# Adafruit_2_13in_Tri-Color_eInk_FeatherWi.net
KiCad netlist of a schematic drawn in EAGLE
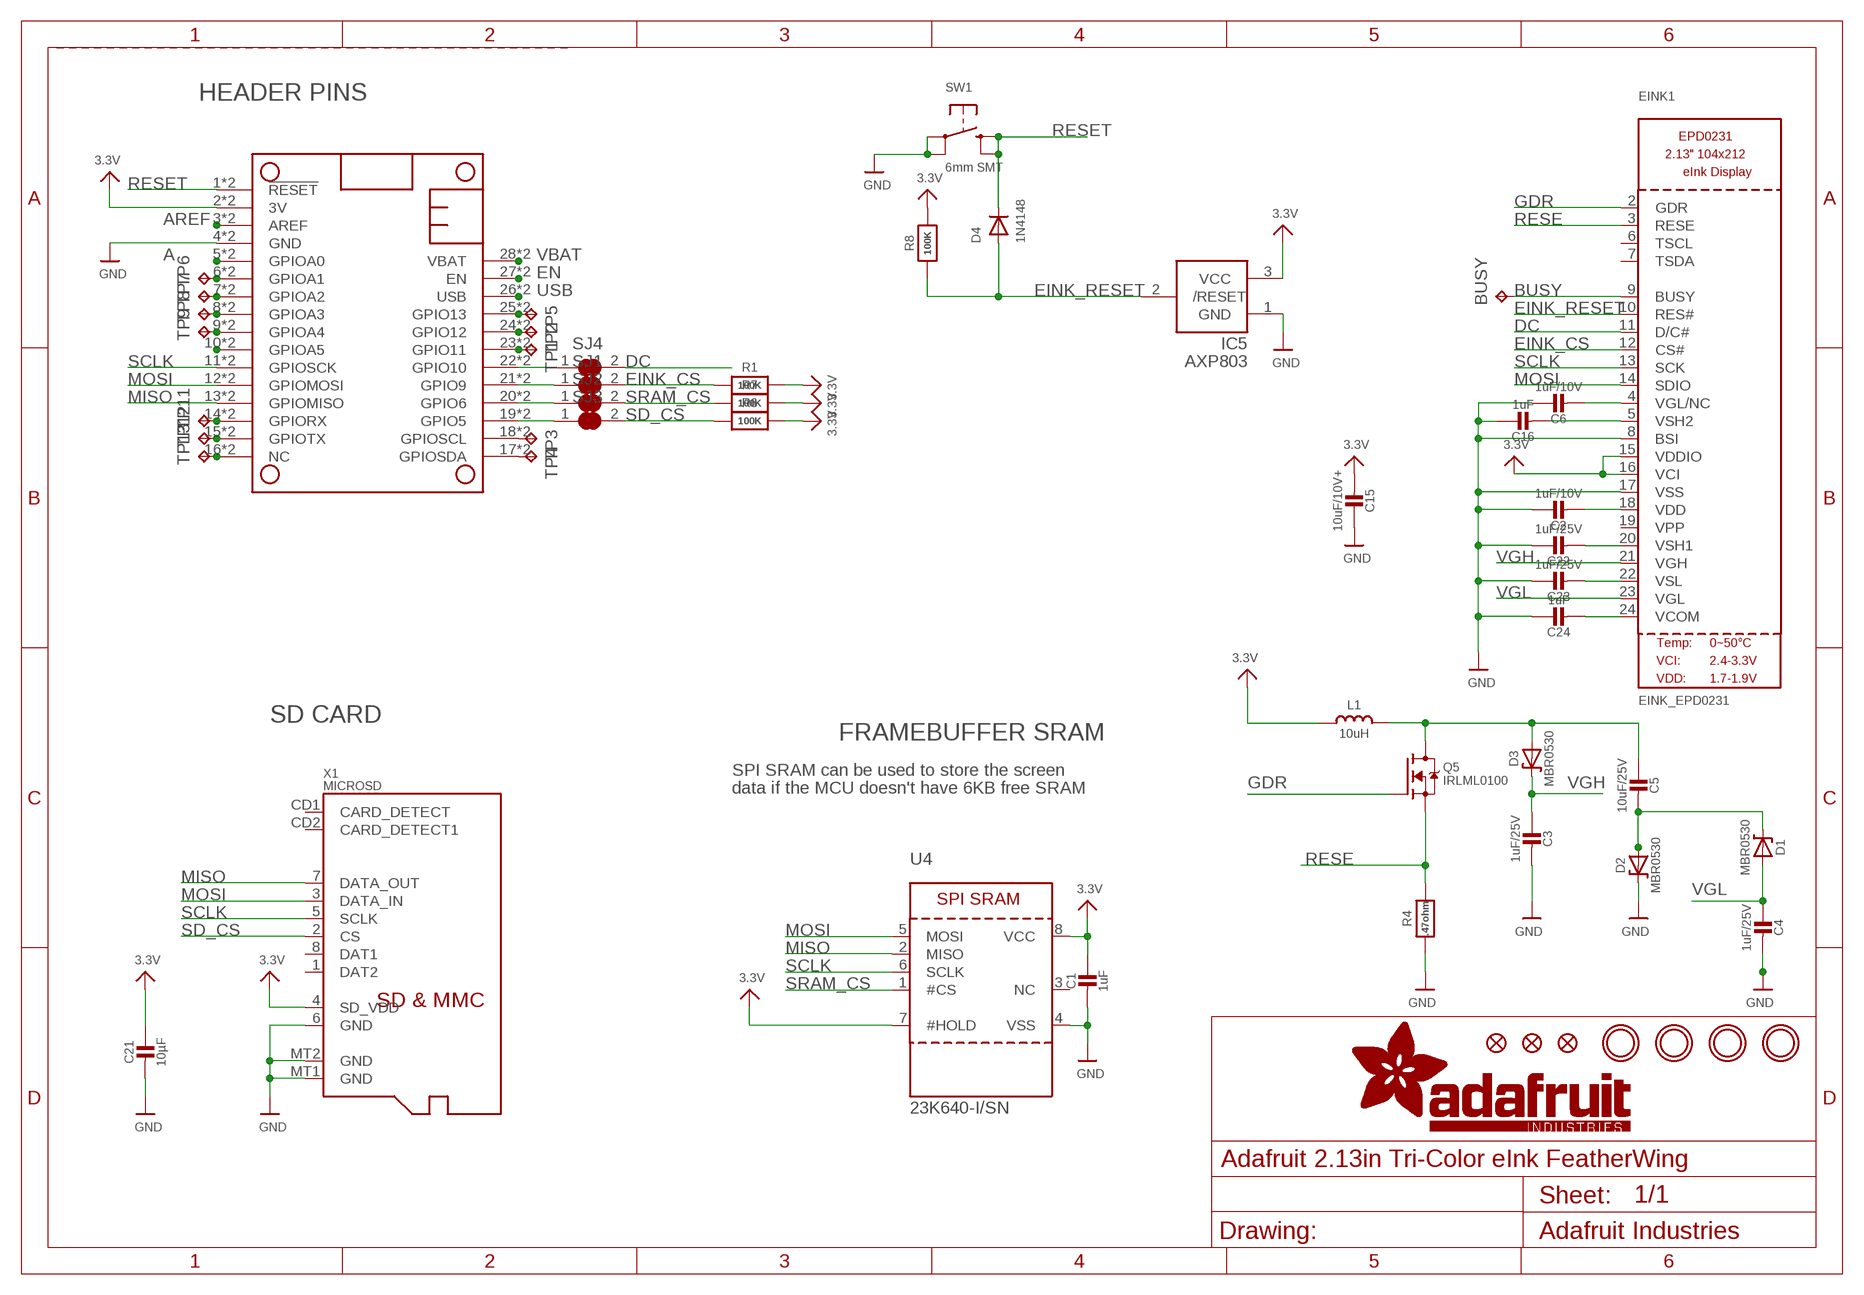
[diagram p0: schematic, sheet 1]

(export (version "E")
  (design (tool "Eeschema 10.0.6"))
  (components
    (comp (ref "BUSY")
      (value "TPTP15SQ")
      (footprint "eagle-import:TP15SQ")
      (libsource (lib "eagle-import") (part "TPTP15SQ"))
    )
    (comp (ref "C1")
      (value "1uF")
      (footprint "eagle-import:0805_10MGAP")
      (libsource (lib "eagle-import") (part "CAP_CERAMIC0805_10MGAP"))
    )
    (comp (ref "C2")
      (value "1uF/10V")
      (footprint "eagle-import:0805-NO")
      (libsource (lib "eagle-import") (part "CAP_CERAMIC0805-NOOUTLINE"))
    )
    (comp (ref "C3")
      (value "1uF/25V")
      (footprint "eagle-import:0805-NO")
      (libsource (lib "eagle-import") (part "CAP_CERAMIC0805-NOOUTLINE"))
    )
    (comp (ref "C4")
      (value "1uF/25V")
      (footprint "eagle-import:0805-NO")
      (libsource (lib "eagle-import") (part "CAP_CERAMIC0805-NOOUTLINE"))
    )
    (comp (ref "C5")
      (value "10uF/25V")
      (footprint "eagle-import:0805-NO")
      (libsource (lib "eagle-import") (part "CAP_CERAMIC0805-NOOUTLINE"))
    )
    (comp (ref "C6")
      (value "1uF/10V")
      (footprint "eagle-import:0805-NO")
      (libsource (lib "eagle-import") (part "CAP_CERAMIC0805-NOOUTLINE"))
    )
    (comp (ref "C15")
      (value "10uF/10V+")
      (footprint "eagle-import:0805-NO")
      (libsource (lib "eagle-import") (part "CAP_CERAMIC0805-NOOUTLINE"))
    )
    (comp (ref "C16")
      (value "1uF")
      (footprint "eagle-import:0805-NO")
      (libsource (lib "eagle-import") (part "CAP_CERAMIC0805-NOOUTLINE"))
    )
    (comp (ref "C21")
      (value "10µF")
      (footprint "eagle-import:0805-NO")
      (libsource (lib "eagle-import") (part "CAP_CERAMIC0805-NOOUTLINE"))
    )
    (comp (ref "C22")
      (value "1uF/25V")
      (footprint "eagle-import:0805-NO")
      (libsource (lib "eagle-import") (part "CAP_CERAMIC0805-NOOUTLINE"))
    )
    (comp (ref "C23")
      (value "1uF/25V")
      (footprint "eagle-import:0805-NO")
      (libsource (lib "eagle-import") (part "CAP_CERAMIC0805-NOOUTLINE"))
    )
    (comp (ref "C24")
      (value "1uF")
      (footprint "eagle-import:0805-NO")
      (libsource (lib "eagle-import") (part "CAP_CERAMIC0805-NOOUTLINE"))
    )
    (comp (ref "D1")
      (value "MBR0530")
      (footprint "eagle-import:SOD-123")
      (libsource (lib "eagle-import") (part "DIODE-SCHOTTKYSOD-123"))
    )
    (comp (ref "D2")
      (value "MBR0530")
      (footprint "eagle-import:SOD-123")
      (libsource (lib "eagle-import") (part "DIODE-SCHOTTKYSOD-123"))
    )
    (comp (ref "D3")
      (value "MBR0530")
      (footprint "eagle-import:SOD-123")
      (libsource (lib "eagle-import") (part "DIODE-SCHOTTKYSOD-123"))
    )
    (comp (ref "D4")
      (value "1N4148")
      (footprint "eagle-import:SOD-323F")
      (libsource (lib "eagle-import") (part "DIODESOD-323F"))
    )
    (comp (ref "EINK1")
      (value "EINK_EPD0231")
      (footprint "eagle-import:EINK_213IN_104X212")
      (libsource (lib "eagle-import") (part "EINK_EPD0231"))
    )
    (comp (ref "FID1")
      (value "FIDUCIAL_1MM")
      (footprint "eagle-import:FIDUCIAL_1MM")
      (libsource (lib "eagle-import") (part "FIDUCIAL_1MM"))
    )
    (comp (ref "FID2")
      (value "FIDUCIAL_1MM")
      (footprint "eagle-import:FIDUCIAL_1MM")
      (libsource (lib "eagle-import") (part "FIDUCIAL_1MM"))
    )
    (comp (ref "FID3")
      (value "FIDUCIAL_1MM")
      (footprint "eagle-import:FIDUCIAL_1MM")
      (libsource (lib "eagle-import") (part "FIDUCIAL_1MM"))
    )
    (comp (ref "IC5")
      (value "AXP803")
      (footprint "eagle-import:SOT23")
      (libsource (lib "eagle-import") (part "AXP083-SAG"))
    )
    (comp (ref "L1")
      (value "10uH")
      (footprint "eagle-import:INDUCTOR_4X4MM_NR401")
      (libsource (lib "eagle-import") (part "INDUCTORNR401"))
    )
    (comp (ref "MS1")
      (value "FEATHERWING_SMTDUALNOHOLES")
      (footprint "eagle-import:FEATHERWING_SMT_NOHOLES")
      (libsource (lib "eagle-import") (part "FEATHERWING_SMTDUALNOHOLES"))
    )
    (comp (ref "Q5")
      (value "IRLML0100")
      (footprint "eagle-import:SOT23-3")
      (libsource (lib "eagle-import") (part "IRLML2060TRPBF"))
    )
    (comp (ref "R1")
      (value "100K")
      (footprint "eagle-import:0603-NO")
      (libsource (lib "eagle-import") (part "RESISTOR_0603_NOOUT"))
    )
    (comp (ref "R4")
      (value ".47ohm")
      (footprint "eagle-import:0805_10MGAP")
      (libsource (lib "eagle-import") (part "RESISTOR0805_10MGAP"))
    )
    (comp (ref "R6")
      (value "100K")
      (footprint "eagle-import:0603-NO")
      (libsource (lib "eagle-import") (part "RESISTOR_0603_NOOUT"))
    )
    (comp (ref "R7")
      (value "100K")
      (footprint "eagle-import:0603-NO")
      (libsource (lib "eagle-import") (part "RESISTOR_0603_NOOUT"))
    )
    (comp (ref "R8")
      (value "100K")
      (footprint "eagle-import:0603-NO")
      (libsource (lib "eagle-import") (part "RESISTOR_0603_NOOUT"))
    )
    (comp (ref "SJ1")
      (value "SOLDERJUMPER_CLOSED")
      (footprint "eagle-import:SOLDERJUMPER_CLOSEDWIRE")
      (libsource (lib "eagle-import") (part "SOLDERJUMPER_CLOSED"))
    )
    (comp (ref "SJ2")
      (value "SOLDERJUMPER_CLOSED")
      (footprint "eagle-import:SOLDERJUMPER_CLOSEDWIRE")
      (libsource (lib "eagle-import") (part "SOLDERJUMPER_CLOSED"))
    )
    (comp (ref "SJ3")
      (value "SOLDERJUMPER_CLOSED")
      (footprint "eagle-import:SOLDERJUMPER_CLOSEDWIRE")
      (libsource (lib "eagle-import") (part "SOLDERJUMPER_CLOSED"))
    )
    (comp (ref "SJ4")
      (value "SOLDERJUMPER_CLOSED")
      (footprint "eagle-import:SOLDERJUMPER_CLOSEDWIRE")
      (libsource (lib "eagle-import") (part "SOLDERJUMPER_CLOSED"))
    )
    (comp (ref "SW1")
      (value "6mm SMT")
      (footprint "eagle-import:EVQ-Q2_SMALLER")
      (libsource (lib "eagle-import") (part "SWITCH_TACT_SMT_EVQQ2_SMALL"))
    )
    (comp (ref "TP1")
      (value "TPTP15SQ")
      (footprint "eagle-import:TP15SQ")
      (libsource (lib "eagle-import") (part "TPTP15SQ"))
    )
    (comp (ref "TP2")
      (value "TPTP15SQ")
      (footprint "eagle-import:TP15SQ")
      (libsource (lib "eagle-import") (part "TPTP15SQ"))
    )
    (comp (ref "TP3")
      (value "TPTP15SQ")
      (footprint "eagle-import:TP15SQ")
      (libsource (lib "eagle-import") (part "TPTP15SQ"))
    )
    (comp (ref "TP4")
      (value "TPTP15SQ")
      (footprint "eagle-import:TP15SQ")
      (libsource (lib "eagle-import") (part "TPTP15SQ"))
    )
    (comp (ref "TP5")
      (value "TPTP15SQ")
      (footprint "eagle-import:TP15SQ")
      (libsource (lib "eagle-import") (part "TPTP15SQ"))
    )
    (comp (ref "TP6")
      (value "TPTP15SQ")
      (footprint "eagle-import:TP15SQ")
      (libsource (lib "eagle-import") (part "TPTP15SQ"))
    )
    (comp (ref "TP7")
      (value "TPTP15SQ")
      (footprint "eagle-import:TP15SQ")
      (libsource (lib "eagle-import") (part "TPTP15SQ"))
    )
    (comp (ref "TP8")
      (value "TPTP15SQ")
      (footprint "eagle-import:TP15SQ")
      (libsource (lib "eagle-import") (part "TPTP15SQ"))
    )
    (comp (ref "TP9")
      (value "TPTP15SQ")
      (footprint "eagle-import:TP15SQ")
      (libsource (lib "eagle-import") (part "TPTP15SQ"))
    )
    (comp (ref "TP11")
      (value "TPTP15SQ")
      (footprint "eagle-import:TP15SQ")
      (libsource (lib "eagle-import") (part "TPTP15SQ"))
    )
    (comp (ref "TP12")
      (value "TPTP15SQ")
      (footprint "eagle-import:TP15SQ")
      (libsource (lib "eagle-import") (part "TPTP15SQ"))
    )
    (comp (ref "TP13")
      (value "TPTP15SQ")
      (footprint "eagle-import:TP15SQ")
      (libsource (lib "eagle-import") (part "TPTP15SQ"))
    )
    (comp (ref "U$3")
      (value "MOUNTINGHOLE2.5")
      (footprint "eagle-import:MOUNTINGHOLE_2.5_PLATED")
      (libsource (lib "eagle-import") (part "MOUNTINGHOLE2.5"))
    )
    (comp (ref "U$4")
      (value "MOUNTINGHOLE2.5")
      (footprint "eagle-import:MOUNTINGHOLE_2.5_PLATED")
      (libsource (lib "eagle-import") (part "MOUNTINGHOLE2.5"))
    )
    (comp (ref "U$5")
      (value "MOUNTINGHOLE2.5")
      (footprint "eagle-import:MOUNTINGHOLE_2.5_PLATED")
      (libsource (lib "eagle-import") (part "MOUNTINGHOLE2.5"))
    )
    (comp (ref "U$6")
      (value "MOUNTINGHOLE2.5")
      (footprint "eagle-import:MOUNTINGHOLE_2.5_PLATED")
      (libsource (lib "eagle-import") (part "MOUNTINGHOLE2.5"))
    )
    (comp (ref "U4")
      (value "23K640-I/SN")
      (footprint "eagle-import:SOIC8_150MIL")
      (libsource (lib "eagle-import") (part "SRAM_SPI_SOIC8"))
    )
    (comp (ref "X1")
      (value "MICROSD")
      (footprint "eagle-import:MICROSD")
      (libsource (lib "eagle-import") (part "MICROSD"))
    )
  )
  (nets
    (net (code "3") (name "/A") (class "Default")
      (node (ref "MS1") (pin "5") (pinfunction "GPIOA0_5") (pintype "bidirectional"))
      (node (ref "MS1") (pin "5B") (pinfunction "GPIOA0_5B") (pintype "bidirectional"))
    )
    (net (code "4") (name "/AREF") (class "Default")
      (node (ref "MS1") (pin "3") (pinfunction "AREF_3") (pintype "passive"))
      (node (ref "MS1") (pin "3B") (pinfunction "AREF_3B") (pintype "passive"))
    )
    (net (code "5") (name "/BUSY") (class "Default")
      (node (ref "BUSY") (pin "TP") (pinfunction "TP_TP") (pintype "input"))
      (node (ref "EINK1") (pin "9") (pinfunction "BUSY_9") (pintype "output"))
    )
    (net (code "6") (name "/DC") (class "Default")
      (node (ref "EINK1") (pin "11") (pinfunction "D/C#_11") (pintype "input"))
      (node (ref "SJ4") (pin "2") (pinfunction "2_2") (pintype "passive"))
    )
    (net (code "8") (name "/EINK_CS") (class "Default")
      (node (ref "EINK1") (pin "12") (pinfunction "CS#_12") (pintype "input"))
      (node (ref "R1") (pin "1") (pinfunction "1_1") (pintype "passive"))
      (node (ref "SJ1") (pin "2") (pinfunction "2_2") (pintype "passive"))
    )
    (net (code "9") (name "/EINK_RESET") (class "Default")
      (node (ref "D4") (pin "A") (pinfunction "A_A") (pintype "passive"))
      (node (ref "EINK1") (pin "10") (pinfunction "RES#_10") (pintype "input"))
      (node (ref "IC5") (pin "2") (pinfunction "/RESET_2") (pintype "output"))
      (node (ref "R8") (pin "1") (pinfunction "1_1") (pintype "passive"))
    )
    (net (code "10") (name "/EN") (class "Default")
      (node (ref "MS1") (pin "27") (pinfunction "EN_27") (pintype "passive"))
      (node (ref "MS1") (pin "27B") (pinfunction "EN_27B") (pintype "passive"))
    )
    (net (code "11") (name "/GDR") (class "Default")
      (node (ref "EINK1") (pin "2") (pinfunction "GDR_2") (pintype "output"))
      (node (ref "Q5") (pin "1") (pinfunction "G_1") (pintype "bidirectional"))
    )
    (net (code "12") (name "/MISO") (class "Default")
      (node (ref "MS1") (pin "13") (pinfunction "GPIOMISO_13") (pintype "bidirectional"))
      (node (ref "MS1") (pin "13B") (pinfunction "GPIOMISO_13B") (pintype "bidirectional"))
      (node (ref "U4") (pin "2") (pinfunction "MISO_2") (pintype "output"))
      (node (ref "X1") (pin "7") (pinfunction "DATA_OUT_7") (pintype "output"))
    )
    (net (code "13") (name "/MOSI") (class "Default")
      (node (ref "EINK1") (pin "14") (pinfunction "SDIO_14") (pintype "bidirectional"))
      (node (ref "MS1") (pin "12") (pinfunction "GPIOMOSI_12") (pintype "bidirectional"))
      (node (ref "MS1") (pin "12B") (pinfunction "GPIOMOSI_12B") (pintype "bidirectional"))
      (node (ref "U4") (pin "5") (pinfunction "MOSI_5") (pintype "input"))
      (node (ref "X1") (pin "3") (pinfunction "DATA_IN_3") (pintype "input"))
    )
    (net (code "14") (name "/RESE") (class "Default")
      (node (ref "EINK1") (pin "3") (pinfunction "RESE_3") (pintype "input"))
      (node (ref "Q5") (pin "2") (pinfunction "S_2") (pintype "bidirectional"))
      (node (ref "R4") (pin "1") (pinfunction "1_1") (pintype "passive"))
    )
    (net (code "15") (name "/RESET") (class "Default")
      (node (ref "D4") (pin "C") (pinfunction "C_C") (pintype "passive"))
      (node (ref "MS1") (pin "1") (pinfunction "~{RESET}_1") (pintype "input"))
      (node (ref "MS1") (pin "1B") (pinfunction "~{RESET}_1B") (pintype "input"))
      (node (ref "SW1") (pin "B") (pinfunction "S_B") (pintype "passive"))
      (node (ref "SW1") (pin "B'") (pinfunction "S1_B'") (pintype "passive"))
    )
    (net (code "18") (name "/SCLK") (class "Default")
      (node (ref "EINK1") (pin "13") (pinfunction "SCK_13") (pintype "bidirectional"))
      (node (ref "MS1") (pin "11") (pinfunction "GPIOSCK_11") (pintype "bidirectional"))
      (node (ref "MS1") (pin "11B") (pinfunction "GPIOSCK_11B") (pintype "bidirectional"))
      (node (ref "U4") (pin "6") (pinfunction "SCLK_6") (pintype "input"))
      (node (ref "X1") (pin "5") (pinfunction "SCLK_5") (pintype "input"))
    )
    (net (code "19") (name "/SD_CS") (class "Default")
      (node (ref "R6") (pin "1") (pinfunction "1_1") (pintype "passive"))
      (node (ref "SJ3") (pin "2") (pinfunction "2_2") (pintype "passive"))
      (node (ref "X1") (pin "2") (pinfunction "CS_2") (pintype "input"))
    )
    (net (code "20") (name "/SRAM_CS") (class "Default")
      (node (ref "R7") (pin "1") (pinfunction "1_1") (pintype "passive"))
      (node (ref "SJ2") (pin "2") (pinfunction "2_2") (pintype "passive"))
      (node (ref "U4") (pin "1") (pinfunction "#CS_1") (pintype "input"))
    )
    (net (code "21") (name "/USB") (class "Default")
      (node (ref "MS1") (pin "26") (pinfunction "USB_26") (pintype "power_in"))
      (node (ref "MS1") (pin "26B") (pinfunction "USB_26B") (pintype "power_in"))
    )
    (net (code "22") (name "/VBAT") (class "Default")
      (node (ref "MS1") (pin "28") (pinfunction "VBAT_28") (pintype "power_in"))
      (node (ref "MS1") (pin "28B") (pinfunction "VBAT_28B") (pintype "power_in"))
    )
    (net (code "23") (name "/VGH") (class "Default")
      (node (ref "C3") (pin "1") (pinfunction "1_1") (pintype "passive"))
      (node (ref "D3") (pin "C") (pinfunction "C_C") (pintype "passive"))
      (node (ref "EINK1") (pin "21") (pinfunction "VGH_21") (pintype "passive"))
    )
    (net (code "24") (name "/VGL") (class "Default")
      (node (ref "C4") (pin "1") (pinfunction "1_1") (pintype "passive"))
      (node (ref "D1") (pin "A") (pinfunction "A_A") (pintype "passive"))
      (node (ref "EINK1") (pin "23") (pinfunction "VGL_23") (pintype "passive"))
    )
    (net (code "25") (name "3.3V") (class "Default")
      (node (ref "C1") (pin "1") (pinfunction "1_1") (pintype "passive"))
      (node (ref "C15") (pin "2") (pinfunction "2_2") (pintype "passive"))
      (node (ref "C21") (pin "1") (pinfunction "1_1") (pintype "passive"))
      (node (ref "EINK1") (pin "15") (pinfunction "VDDIO_15") (pintype "power_in"))
      (node (ref "EINK1") (pin "16") (pinfunction "VCI_16") (pintype "power_in"))
      (node (ref "IC5") (pin "3") (pinfunction "VCC_3") (pintype "power_in"))
      (node (ref "L1") (pin "P$2") (pinfunction "2_P$2") (pintype "passive"))
      (node (ref "MS1") (pin "2") (pinfunction "3V_2") (pintype "power_in"))
      (node (ref "MS1") (pin "2B") (pinfunction "3V_2B") (pintype "power_in"))
      (node (ref "R1") (pin "2") (pinfunction "2_2") (pintype "passive"))
      (node (ref "R6") (pin "2") (pinfunction "2_2") (pintype "passive"))
      (node (ref "R7") (pin "2") (pinfunction "2_2") (pintype "passive"))
      (node (ref "R8") (pin "2") (pinfunction "2_2") (pintype "passive"))
      (node (ref "U4") (pin "7") (pinfunction "#HOLD_7") (pintype "input"))
      (node (ref "U4") (pin "8") (pinfunction "VCC_8") (pintype "power_in"))
      (node (ref "X1") (pin "4") (pinfunction "SD_VDD_4") (pintype "power_in"))
    )
    (net (code "26") (name "GND") (class "Default")
      (node (ref "C1") (pin "2") (pinfunction "2_2") (pintype "passive"))
      (node (ref "C15") (pin "1") (pinfunction "1_1") (pintype "passive"))
      (node (ref "C16") (pin "1") (pinfunction "1_1") (pintype "passive"))
      (node (ref "C2") (pin "1") (pinfunction "1_1") (pintype "passive"))
      (node (ref "C21") (pin "2") (pinfunction "2_2") (pintype "passive"))
      (node (ref "C22") (pin "1") (pinfunction "1_1") (pintype "passive"))
      (node (ref "C23") (pin "1") (pinfunction "1_1") (pintype "passive"))
      (node (ref "C24") (pin "1") (pinfunction "1_1") (pintype "passive"))
      (node (ref "C3") (pin "2") (pinfunction "2_2") (pintype "passive"))
      (node (ref "C4") (pin "2") (pinfunction "2_2") (pintype "passive"))
      (node (ref "C6") (pin "1") (pinfunction "1_1") (pintype "passive"))
      (node (ref "D2") (pin "C") (pinfunction "C_C") (pintype "passive"))
      (node (ref "EINK1") (pin "17") (pinfunction "VSS_17") (pintype "power_in"))
      (node (ref "EINK1") (pin "8") (pinfunction "BSI_8") (pintype "input"))
      (node (ref "IC5") (pin "1") (pinfunction "GND_1") (pintype "power_in"))
      (node (ref "MS1") (pin "4") (pinfunction "GND_4") (pintype "power_in"))
      (node (ref "MS1") (pin "4B") (pinfunction "GND_4B") (pintype "power_in"))
      (node (ref "R4") (pin "2") (pinfunction "2_2") (pintype "passive"))
      (node (ref "SW1") (pin "A") (pinfunction "P_A") (pintype "passive"))
      (node (ref "SW1") (pin "A'") (pinfunction "P1_A'") (pintype "passive"))
      (node (ref "U4") (pin "4") (pinfunction "VSS_4") (pintype "power_in"))
      (node (ref "X1") (pin "6") (pinfunction "GND_6") (pintype "power_in"))
      (node (ref "X1") (pin "MT1") (pinfunction "GND_MT1") (pintype "power_in"))
      (node (ref "X1") (pin "MT2") (pinfunction "GND_MT2") (pintype "power_in"))
    )
    (net (code "27") (name "Net-(C5-Pad2)") (class "Default")
      (node (ref "C5") (pin "2") (pinfunction "2_2") (pintype "passive"))
      (node (ref "D1") (pin "C") (pinfunction "C_C") (pintype "passive"))
      (node (ref "D2") (pin "A") (pinfunction "A_A") (pintype "passive"))
    )
    (net (code "28") (name "Net-(EINK1-VCOM)") (class "Default")
      (node (ref "C24") (pin "2") (pinfunction "2_2") (pintype "passive"))
      (node (ref "EINK1") (pin "24") (pinfunction "VCOM_24") (pintype "passive"))
    )
    (net (code "29") (name "Net-(EINK1-VDD)") (class "Default")
      (node (ref "C2") (pin "2") (pinfunction "2_2") (pintype "passive"))
      (node (ref "EINK1") (pin "18") (pinfunction "VDD_18") (pintype "passive"))
    )
    (net (code "30") (name "Net-(EINK1-VGL{slash}NC)") (class "Default")
      (node (ref "C6") (pin "2") (pinfunction "2_2") (pintype "passive"))
      (node (ref "EINK1") (pin "4") (pinfunction "VGL/NC_4") (pintype "bidirectional"))
    )
    (net (code "31") (name "Net-(EINK1-VSH1)") (class "Default")
      (node (ref "C22") (pin "2") (pinfunction "2_2") (pintype "passive"))
      (node (ref "EINK1") (pin "20") (pinfunction "VSH1_20") (pintype "passive"))
    )
    (net (code "32") (name "Net-(EINK1-VSH2)") (class "Default")
      (node (ref "C16") (pin "2") (pinfunction "2_2") (pintype "passive"))
      (node (ref "EINK1") (pin "5") (pinfunction "VSH2_5") (pintype "passive"))
    )
    (net (code "33") (name "Net-(EINK1-VSL)") (class "Default")
      (node (ref "C23") (pin "2") (pinfunction "2_2") (pintype "passive"))
      (node (ref "EINK1") (pin "22") (pinfunction "VSL_22") (pintype "passive"))
    )
    (net (code "34") (name "Net-(L1-1)") (class "Default")
      (node (ref "C5") (pin "1") (pinfunction "1_1") (pintype "passive"))
      (node (ref "D3") (pin "A") (pinfunction "A_A") (pintype "passive"))
      (node (ref "L1") (pin "P$1") (pinfunction "1_P$1") (pintype "passive"))
      (node (ref "Q5") (pin "3") (pinfunction "D_3") (pintype "bidirectional"))
    )
    (net (code "35") (name "Net-(MS1-GPIO5-Pad19)") (class "Default")
      (node (ref "MS1") (pin "19") (pinfunction "GPIO5_19") (pintype "bidirectional"))
      (node (ref "MS1") (pin "19B") (pinfunction "GPIO5_19B") (pintype "bidirectional"))
      (node (ref "SJ3") (pin "1") (pinfunction "1_1") (pintype "passive"))
    )
    (net (code "36") (name "Net-(MS1-GPIO6-Pad20)") (class "Default")
      (node (ref "MS1") (pin "20") (pinfunction "GPIO6_20") (pintype "bidirectional"))
      (node (ref "MS1") (pin "20B") (pinfunction "GPIO6_20B") (pintype "bidirectional"))
      (node (ref "SJ2") (pin "1") (pinfunction "1_1") (pintype "passive"))
    )
    (net (code "37") (name "Net-(MS1-GPIO9-Pad21)") (class "Default")
      (node (ref "MS1") (pin "21") (pinfunction "GPIO9_21") (pintype "bidirectional"))
      (node (ref "MS1") (pin "21B") (pinfunction "GPIO9_21B") (pintype "bidirectional"))
      (node (ref "SJ1") (pin "1") (pinfunction "1_1") (pintype "passive"))
    )
    (net (code "38") (name "Net-(MS1-GPIO10-Pad22)") (class "Default")
      (node (ref "MS1") (pin "22") (pinfunction "GPIO10_22") (pintype "bidirectional"))
      (node (ref "MS1") (pin "22B") (pinfunction "GPIO10_22B") (pintype "bidirectional"))
      (node (ref "SJ4") (pin "1") (pinfunction "1_1") (pintype "passive"))
    )
    (net (code "39") (name "Net-(MS1-GPIO11-Pad23)") (class "Default")
      (node (ref "MS1") (pin "23") (pinfunction "GPIO11_23") (pintype "bidirectional"))
      (node (ref "MS1") (pin "23B") (pinfunction "GPIO11_23B") (pintype "bidirectional"))
      (node (ref "TP1") (pin "TP") (pinfunction "TP_TP") (pintype "input"))
    )
    (net (code "40") (name "Net-(MS1-GPIO12-Pad24)") (class "Default")
      (node (ref "MS1") (pin "24") (pinfunction "GPIO12_24") (pintype "bidirectional"))
      (node (ref "MS1") (pin "24B") (pinfunction "GPIO12_24B") (pintype "bidirectional"))
      (node (ref "TP2") (pin "TP") (pinfunction "TP_TP") (pintype "input"))
    )
    (net (code "41") (name "Net-(MS1-GPIO13-Pad25)") (class "Default")
      (node (ref "MS1") (pin "25") (pinfunction "GPIO13_25") (pintype "bidirectional"))
      (node (ref "MS1") (pin "25B") (pinfunction "GPIO13_25B") (pintype "bidirectional"))
      (node (ref "TP5") (pin "TP") (pinfunction "TP_TP") (pintype "input"))
    )
    (net (code "42") (name "Net-(MS1-GPIOA1-Pad6)") (class "Default")
      (node (ref "MS1") (pin "6") (pinfunction "GPIOA1_6") (pintype "bidirectional"))
      (node (ref "MS1") (pin "6B") (pinfunction "GPIOA1_6B") (pintype "bidirectional"))
      (node (ref "TP6") (pin "TP") (pinfunction "TP_TP") (pintype "input"))
    )
    (net (code "43") (name "Net-(MS1-GPIOA2-Pad7)") (class "Default")
      (node (ref "MS1") (pin "7") (pinfunction "GPIOA2_7") (pintype "bidirectional"))
      (node (ref "MS1") (pin "7B") (pinfunction "GPIOA2_7B") (pintype "bidirectional"))
      (node (ref "TP7") (pin "TP") (pinfunction "TP_TP") (pintype "input"))
    )
    (net (code "44") (name "Net-(MS1-GPIOA3-Pad8)") (class "Default")
      (node (ref "MS1") (pin "8") (pinfunction "GPIOA3_8") (pintype "bidirectional"))
      (node (ref "MS1") (pin "8B") (pinfunction "GPIOA3_8B") (pintype "bidirectional"))
      (node (ref "TP8") (pin "TP") (pinfunction "TP_TP") (pintype "input"))
    )
    (net (code "45") (name "Net-(MS1-GPIOA4-Pad9)") (class "Default")
      (node (ref "MS1") (pin "9") (pinfunction "GPIOA4_9") (pintype "bidirectional"))
      (node (ref "MS1") (pin "9B") (pinfunction "GPIOA4_9B") (pintype "bidirectional"))
      (node (ref "TP9") (pin "TP") (pinfunction "TP_TP") (pintype "input"))
    )
    (net (code "46") (name "Net-(MS1-GPIOA5-Pad10)") (class "Default")
      (node (ref "MS1") (pin "10") (pinfunction "GPIOA5_10") (pintype "bidirectional"))
      (node (ref "MS1") (pin "10B") (pinfunction "GPIOA5_10B") (pintype "bidirectional"))
    )
    (net (code "47") (name "Net-(MS1-GPIORX-Pad14)") (class "Default")
      (node (ref "MS1") (pin "14") (pinfunction "GPIORX_14") (pintype "bidirectional"))
      (node (ref "MS1") (pin "14B") (pinfunction "GPIORX_14B") (pintype "bidirectional"))
      (node (ref "TP11") (pin "TP") (pinfunction "TP_TP") (pintype "input"))
    )
    (net (code "48") (name "Net-(MS1-GPIOSCL-Pad18)") (class "Default")
      (node (ref "MS1") (pin "18") (pinfunction "GPIOSCL_18") (pintype "bidirectional"))
      (node (ref "MS1") (pin "18B") (pinfunction "GPIOSCL_18B") (pintype "bidirectional"))
      (node (ref "TP3") (pin "TP") (pinfunction "TP_TP") (pintype "input"))
    )
    (net (code "49") (name "Net-(MS1-GPIOSDA-Pad17)") (class "Default")
      (node (ref "MS1") (pin "17") (pinfunction "GPIOSDA_17") (pintype "bidirectional"))
      (node (ref "MS1") (pin "17B") (pinfunction "GPIOSDA_17B") (pintype "bidirectional"))
      (node (ref "TP4") (pin "TP") (pinfunction "TP_TP") (pintype "input"))
    )
    (net (code "50") (name "Net-(MS1-GPIOTX-Pad15)") (class "Default")
      (node (ref "MS1") (pin "15") (pinfunction "GPIOTX_15") (pintype "bidirectional"))
      (node (ref "MS1") (pin "15B") (pinfunction "GPIOTX_15B") (pintype "bidirectional"))
      (node (ref "TP12") (pin "TP") (pinfunction "TP_TP") (pintype "input"))
    )
    (net (code "51") (name "Net-(MS1-NC-Pad16)") (class "Default")
      (node (ref "MS1") (pin "16") (pinfunction "NC_16") (pintype "passive"))
      (node (ref "MS1") (pin "16B") (pinfunction "NC_16B") (pintype "passive"))
      (node (ref "TP13") (pin "TP") (pinfunction "TP_TP") (pintype "input"))
    )
    (net (code "52") (name "unconnected-(EINK1-TSCL-Pad6)") (class "Default")
      (node (ref "EINK1") (pin "6") (pinfunction "TSCL_6") (pintype "output"))
    )
    (net (code "53") (name "unconnected-(EINK1-TSDA-Pad7)") (class "Default")
      (node (ref "EINK1") (pin "7") (pinfunction "TSDA_7") (pintype "bidirectional"))
    )
    (net (code "54") (name "unconnected-(EINK1-VPP-Pad19)") (class "Default")
      (node (ref "EINK1") (pin "19") (pinfunction "VPP_19") (pintype "passive"))
    )
    (net (code "55") (name "unconnected-(U4-NC-Pad3)") (class "Default")
      (node (ref "U4") (pin "3") (pinfunction "NC_3") (pintype "no_connect"))
    )
    (net (code "56") (name "unconnected-(X1-CARD_DETECT-PadCD1)") (class "Default")
      (node (ref "X1") (pin "CD1") (pinfunction "CARD_DETECT_CD1") (pintype "passive"))
    )
    (net (code "57") (name "unconnected-(X1-CARD_DETECT1-PadCD2)") (class "Default")
      (node (ref "X1") (pin "CD2") (pinfunction "CARD_DETECT1_CD2") (pintype "passive"))
    )
    (net (code "58") (name "unconnected-(X1-DAT1-Pad8)") (class "Default")
      (node (ref "X1") (pin "8") (pinfunction "DAT1_8") (pintype "bidirectional"))
    )
    (net (code "59") (name "unconnected-(X1-DAT2-Pad1)") (class "Default")
      (node (ref "X1") (pin "1") (pinfunction "DAT2_1") (pintype "bidirectional"))
    )
  )
)
